# TapTempo.net
KiCad netlist of a schematic drawn in EAGLE
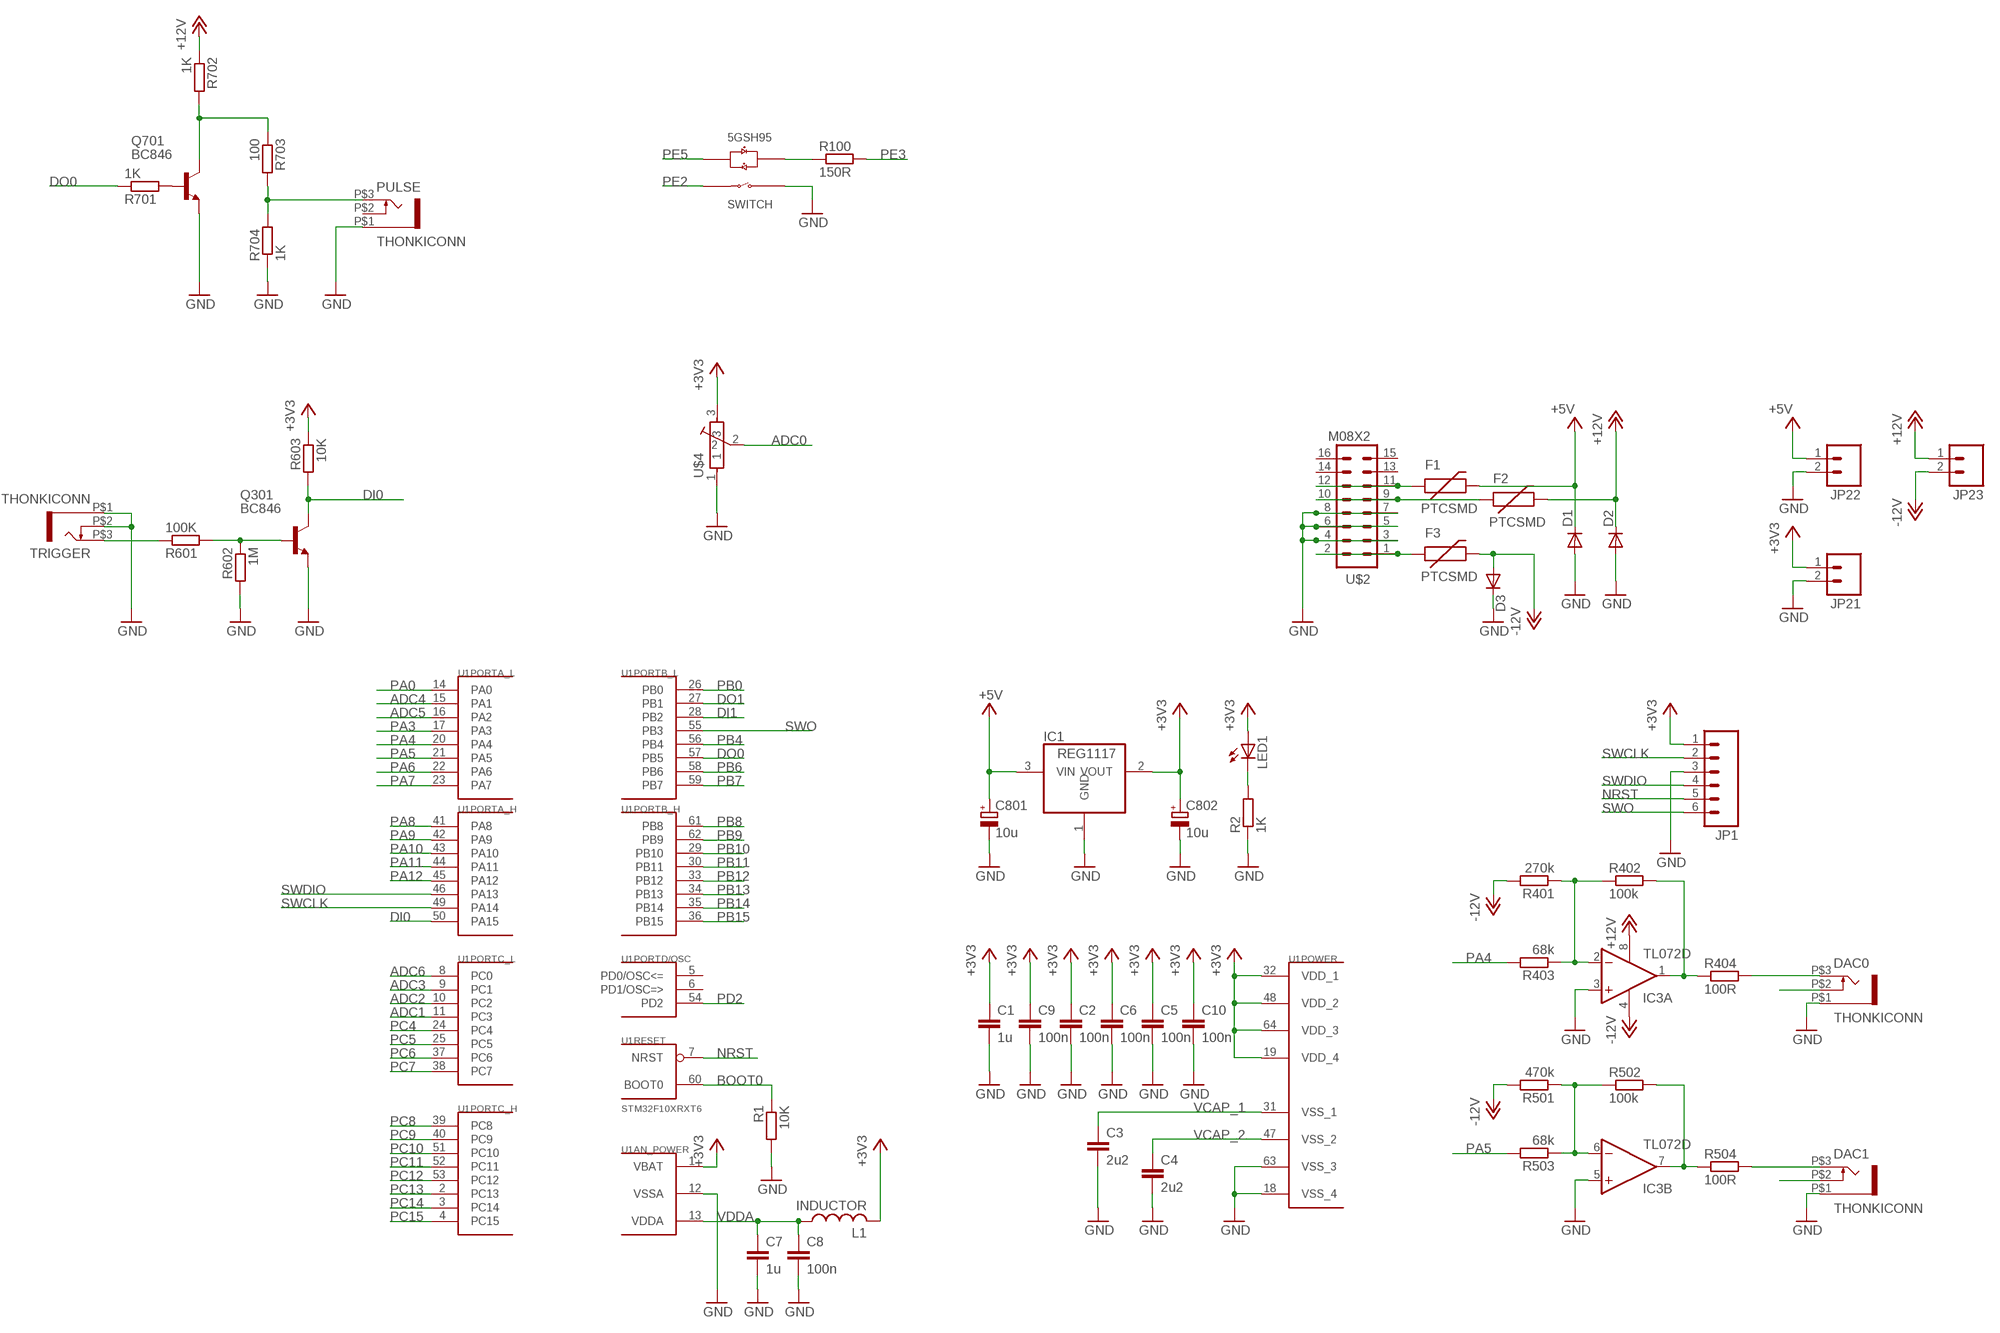
[diagram p0: schematic, sheet 1]

(export (version "E")
  (design (tool "Eeschema 10.0.6"))
  (components
    (comp (ref "C1")
      (value "1u")
      (footprint "eagle-import:C0603")
      (libsource (lib "eagle-import") (part "C-EUC0603"))
    )
    (comp (ref "C2")
      (value "100n")
      (footprint "eagle-import:C0603")
      (libsource (lib "eagle-import") (part "C-EUC0603"))
    )
    (comp (ref "C3")
      (value "2u2")
      (footprint "eagle-import:C0603")
      (libsource (lib "eagle-import") (part "C-EUC0603"))
    )
    (comp (ref "C4")
      (value "2u2")
      (footprint "eagle-import:C0603")
      (libsource (lib "eagle-import") (part "C-EUC0603"))
    )
    (comp (ref "C5")
      (value "100n")
      (footprint "eagle-import:C0603")
      (libsource (lib "eagle-import") (part "C-EUC0603"))
    )
    (comp (ref "C6")
      (value "100n")
      (footprint "eagle-import:C0603")
      (libsource (lib "eagle-import") (part "C-EUC0603"))
    )
    (comp (ref "C7")
      (value "1u")
      (footprint "eagle-import:C0603")
      (libsource (lib "eagle-import") (part "C-EUC0603"))
    )
    (comp (ref "C8")
      (value "100n")
      (footprint "eagle-import:C0603")
      (libsource (lib "eagle-import") (part "C-EUC0603"))
    )
    (comp (ref "C9")
      (value "100n")
      (footprint "eagle-import:C0603")
      (libsource (lib "eagle-import") (part "C-EUC0603"))
    )
    (comp (ref "C10")
      (value "100n")
      (footprint "eagle-import:C0603")
      (libsource (lib "eagle-import") (part "C-EUC0603"))
    )
    (comp (ref "C801")
      (value "10u")
      (footprint "eagle-import:PANASONIC_A")
      (libsource (lib "eagle-import") (part "CPOL-EUA"))
    )
    (comp (ref "C802")
      (value "10u")
      (footprint "eagle-import:PANASONIC_A")
      (libsource (lib "eagle-import") (part "CPOL-EUA"))
    )
    (comp (ref "D1")
      (value "DIODESMA")
      (footprint "eagle-import:SMA-DIODE")
      (libsource (lib "eagle-import") (part "DIODESMA"))
    )
    (comp (ref "D2")
      (value "DIODESMA")
      (footprint "eagle-import:SMA-DIODE")
      (libsource (lib "eagle-import") (part "DIODESMA"))
    )
    (comp (ref "D3")
      (value "DIODESMA")
      (footprint "eagle-import:SMA-DIODE")
      (libsource (lib "eagle-import") (part "DIODESMA"))
    )
    (comp (ref "DAC0")
      (value "THONKICONN")
      (footprint "eagle-import:THONKICONN")
      (libsource (lib "eagle-import") (part "THONKICONN"))
    )
    (comp (ref "DAC1")
      (value "THONKICONN")
      (footprint "eagle-import:THONKICONN")
      (libsource (lib "eagle-import") (part "THONKICONN"))
    )
    (comp (ref "F1")
      (value "PTCSMD")
      (footprint "eagle-import:PTC-1206")
      (libsource (lib "eagle-import") (part "PTCSMD"))
    )
    (comp (ref "F2")
      (value "PTCSMD")
      (footprint "eagle-import:PTC-1206")
      (libsource (lib "eagle-import") (part "PTCSMD"))
    )
    (comp (ref "F3")
      (value "PTCSMD")
      (footprint "eagle-import:PTC-1206")
      (libsource (lib "eagle-import") (part "PTCSMD"))
    )
    (comp (ref "IC1")
      (value "REG1117")
      (footprint "eagle-import:SOT223")
      (libsource (lib "eagle-import") (part "REG1117"))
    )
    (comp (ref "IC3")
      (value "TL072D")
      (footprint "eagle-import:SO08")
      (libsource (lib "eagle-import") (part "TL072D"))
    )
    (comp (ref "JP1")
      (value "M06SIP")
      (footprint "eagle-import:1X06")
      (libsource (lib "eagle-import") (part "M06SIP"))
    )
    (comp (ref "JP21")
      (value "M02PTH")
      (footprint "eagle-import:1X02")
      (libsource (lib "eagle-import") (part "M02PTH"))
    )
    (comp (ref "JP22")
      (value "M02PTH")
      (footprint "eagle-import:1X02")
      (libsource (lib "eagle-import") (part "M02PTH"))
    )
    (comp (ref "JP23")
      (value "M02PTH")
      (footprint "eagle-import:1X02")
      (libsource (lib "eagle-import") (part "M02PTH"))
    )
    (comp (ref "L1")
      (value "INDUCTOR")
      (footprint "eagle-import:0603@1")
      (libsource (lib "eagle-import") (part "INDUCTOR"))
    )
    (comp (ref "LED1")
      (value "LEDCHIPLED_0603")
      (footprint "eagle-import:CHIPLED_0603")
      (libsource (lib "eagle-import") (part "LEDCHIPLED_0603"))
    )
    (comp (ref "PULSE")
      (value "THONKICONN")
      (footprint "eagle-import:THONKICONN")
      (libsource (lib "eagle-import") (part "THONKICONN"))
    )
    (comp (ref "Q301")
      (value "BC846")
      (footprint "eagle-import:SOT23")
      (libsource (lib "eagle-import") (part "BC846"))
    )
    (comp (ref "Q701")
      (value "BC846")
      (footprint "eagle-import:SOT23")
      (libsource (lib "eagle-import") (part "BC846"))
    )
    (comp (ref "R1")
      (value "10K")
      (footprint "eagle-import:R0603")
      (libsource (lib "eagle-import") (part "R-EU_R0603"))
    )
    (comp (ref "R2")
      (value "1K")
      (footprint "eagle-import:R0603")
      (libsource (lib "eagle-import") (part "R-EU_R0603"))
    )
    (comp (ref "R100")
      (value "150R")
      (footprint "eagle-import:0603")
      (libsource (lib "eagle-import") (part "R-EU_0603"))
    )
    (comp (ref "R401")
      (value "270k")
      (footprint "eagle-import:R0603")
      (libsource (lib "eagle-import") (part "R-EU_R0603"))
    )
    (comp (ref "R402")
      (value "100k")
      (footprint "eagle-import:R0603")
      (libsource (lib "eagle-import") (part "R-EU_R0603"))
    )
    (comp (ref "R403")
      (value "68k")
      (footprint "eagle-import:R0603")
      (libsource (lib "eagle-import") (part "R-EU_R0603"))
    )
    (comp (ref "R404")
      (value "100R")
      (footprint "eagle-import:R0603")
      (libsource (lib "eagle-import") (part "R-EU_R0603"))
    )
    (comp (ref "R501")
      (value "470k")
      (footprint "eagle-import:R0603")
      (libsource (lib "eagle-import") (part "R-EU_R0603"))
    )
    (comp (ref "R502")
      (value "100k")
      (footprint "eagle-import:R0603")
      (libsource (lib "eagle-import") (part "R-EU_R0603"))
    )
    (comp (ref "R503")
      (value "68k")
      (footprint "eagle-import:R0603")
      (libsource (lib "eagle-import") (part "R-EU_R0603"))
    )
    (comp (ref "R504")
      (value "100R")
      (footprint "eagle-import:R0603")
      (libsource (lib "eagle-import") (part "R-EU_R0603"))
    )
    (comp (ref "R601")
      (value "100K")
      (footprint "eagle-import:R0603")
      (libsource (lib "eagle-import") (part "R-EU_R0603"))
    )
    (comp (ref "R602")
      (value "1M")
      (footprint "eagle-import:R0603")
      (libsource (lib "eagle-import") (part "R-EU_R0603"))
    )
    (comp (ref "R603")
      (value "10K")
      (footprint "eagle-import:R0603")
      (libsource (lib "eagle-import") (part "R-EU_R0603"))
    )
    (comp (ref "R701")
      (value "1K")
      (footprint "eagle-import:R0603")
      (libsource (lib "eagle-import") (part "R-EU_R0603"))
    )
    (comp (ref "R702")
      (value "1K")
      (footprint "eagle-import:R0603")
      (libsource (lib "eagle-import") (part "R-EU_R0603"))
    )
    (comp (ref "R703")
      (value "100")
      (footprint "eagle-import:R0603")
      (libsource (lib "eagle-import") (part "R-EU_R0603"))
    )
    (comp (ref "R704")
      (value "1K")
      (footprint "eagle-import:R0603")
      (libsource (lib "eagle-import") (part "R-EU_R0603"))
    )
    (comp (ref "TRIGGER")
      (value "THONKICONN")
      (footprint "eagle-import:THONKICONN")
      (libsource (lib "eagle-import") (part "THONKICONN"))
    )
    (comp (ref "U$1")
      (value "5GTH9")
      (footprint "eagle-import:5GTH9")
      (libsource (lib "eagle-import") (part "5GTH9"))
    )
    (comp (ref "U$2")
      (value "M08X2")
      (footprint "eagle-import:2X8")
      (libsource (lib "eagle-import") (part "M08X2"))
    )
    (comp (ref "U$4")
      (value "POT-ALPS-RK09L1140")
      (footprint "eagle-import:POT-ALPS-RK09L1140")
      (libsource (lib "eagle-import") (part "POT-ALPS-RK09L1140"))
    )
    (comp (ref "U1")
      (value "STM32F10XRXT6")
      (footprint "eagle-import:TQFP64")
      (libsource (lib "eagle-import") (part "STM32F10XRXT6"))
    )
  )
  (nets
    (net (code "1") (name "+3V3") (class "Default")
      (node (ref "C1") (pin "1") (pinfunction "1_1") (pintype "passive"))
      (node (ref "C10") (pin "1") (pinfunction "1_1") (pintype "passive"))
      (node (ref "C2") (pin "1") (pinfunction "1_1") (pintype "passive"))
      (node (ref "C5") (pin "1") (pinfunction "1_1") (pintype "passive"))
      (node (ref "C6") (pin "1") (pinfunction "1_1") (pintype "passive"))
      (node (ref "C802") (pin "+") (pinfunction "+_+") (pintype "passive"))
      (node (ref "C9") (pin "1") (pinfunction "1_1") (pintype "passive"))
      (node (ref "IC1") (pin "2") (pinfunction "VOUT_2") (pintype "output"))
      (node (ref "JP1") (pin "1") (pinfunction "1_1") (pintype "passive"))
      (node (ref "JP21") (pin "1") (pinfunction "1_1") (pintype "passive"))
      (node (ref "L1") (pin "2") (pinfunction "2_2") (pintype "passive"))
      (node (ref "LED1") (pin "A") (pinfunction "A_A") (pintype "passive"))
      (node (ref "R603") (pin "1") (pinfunction "1_1") (pintype "passive"))
      (node (ref "U$4") (pin "3") (pinfunction "3_3") (pintype "bidirectional"))
      (node (ref "U1") (pin "1") (pinfunction "VBAT_1") (pintype "power_in"))
      (node (ref "U1") (pin "19") (pinfunction "VDD_4_19") (pintype "power_in"))
      (node (ref "U1") (pin "32") (pinfunction "VDD_1_32") (pintype "power_in"))
      (node (ref "U1") (pin "48") (pinfunction "VDD_2_48") (pintype "power_in"))
      (node (ref "U1") (pin "64") (pinfunction "VDD_3_64") (pintype "power_in"))
    )
    (net (code "2") (name "+5V") (class "Default")
      (node (ref "C801") (pin "+") (pinfunction "+_+") (pintype "passive"))
      (node (ref "D1") (pin "C") (pinfunction "C_C") (pintype "passive"))
      (node (ref "F1") (pin "2") (pinfunction "2_2") (pintype "bidirectional"))
      (node (ref "IC1") (pin "3") (pinfunction "VIN_3") (pintype "input"))
      (node (ref "JP22") (pin "1") (pinfunction "1_1") (pintype "passive"))
    )
    (net (code "3") (name "+12V") (class "Default")
      (node (ref "D2") (pin "C") (pinfunction "C_C") (pintype "passive"))
      (node (ref "F2") (pin "2") (pinfunction "2_2") (pintype "bidirectional"))
      (node (ref "IC3") (pin "8") (pinfunction "V+_8") (pintype "power_in"))
      (node (ref "JP23") (pin "1") (pinfunction "1_1") (pintype "passive"))
      (node (ref "R702") (pin "1") (pinfunction "1_1") (pintype "passive"))
    )
    (net (code "4") (name "-12V") (class "Default")
      (node (ref "D3") (pin "A") (pinfunction "A_A") (pintype "passive"))
      (node (ref "F3") (pin "2") (pinfunction "2_2") (pintype "bidirectional"))
      (node (ref "IC3") (pin "4") (pinfunction "V-_4") (pintype "power_in"))
      (node (ref "JP23") (pin "2") (pinfunction "2_2") (pintype "passive"))
      (node (ref "R401") (pin "2") (pinfunction "2_2") (pintype "passive"))
      (node (ref "R501") (pin "2") (pinfunction "2_2") (pintype "passive"))
    )
    (net (code "5") (name "/ADC0") (class "Default")
      (node (ref "U$4") (pin "2") (pinfunction "2_2") (pintype "bidirectional"))
    )
    (net (code "6") (name "/ADC1") (class "Default")
      (node (ref "U1") (pin "11") (pinfunction "PC3_11") (pintype "bidirectional"))
    )
    (net (code "7") (name "/ADC2") (class "Default")
      (node (ref "U1") (pin "10") (pinfunction "PC2_10") (pintype "bidirectional"))
    )
    (net (code "8") (name "/ADC3") (class "Default")
      (node (ref "U1") (pin "9") (pinfunction "PC1_9") (pintype "bidirectional"))
    )
    (net (code "9") (name "/ADC4") (class "Default")
      (node (ref "U1") (pin "15") (pinfunction "PA1_15") (pintype "bidirectional"))
    )
    (net (code "10") (name "/ADC5") (class "Default")
      (node (ref "U1") (pin "16") (pinfunction "PA2_16") (pintype "bidirectional"))
    )
    (net (code "11") (name "/ADC6") (class "Default")
      (node (ref "U1") (pin "8") (pinfunction "PC0_8") (pintype "bidirectional"))
    )
    (net (code "12") (name "/BOOT0") (class "Default")
      (node (ref "R1") (pin "1") (pinfunction "1_1") (pintype "passive"))
      (node (ref "U1") (pin "60") (pinfunction "BOOT0_60") (pintype "input"))
    )
    (net (code "13") (name "/DI0") (class "Default")
      (node (ref "Q301") (pin "3") (pinfunction "C_3") (pintype "passive"))
      (node (ref "R603") (pin "2") (pinfunction "2_2") (pintype "passive"))
      (node (ref "U1") (pin "50") (pinfunction "PA15_50") (pintype "bidirectional"))
    )
    (net (code "14") (name "/DI1") (class "Default")
      (node (ref "U1") (pin "28") (pinfunction "PB2_28") (pintype "bidirectional"))
    )
    (net (code "15") (name "/DO0") (class "Default")
      (node (ref "R701") (pin "1") (pinfunction "1_1") (pintype "passive"))
      (node (ref "U1") (pin "57") (pinfunction "PB5_57") (pintype "bidirectional"))
    )
    (net (code "16") (name "/DO1") (class "Default")
      (node (ref "U1") (pin "27") (pinfunction "PB1_27") (pintype "bidirectional"))
    )
    (net (code "17") (name "/NRST") (class "Default")
      (node (ref "JP1") (pin "5") (pinfunction "5_5") (pintype "passive"))
      (node (ref "U1") (pin "7") (pinfunction "NRST_7") (pintype "input"))
    )
    (net (code "18") (name "/PA0") (class "Default")
      (node (ref "U1") (pin "14") (pinfunction "PA0_14") (pintype "bidirectional"))
    )
    (net (code "19") (name "/PA3") (class "Default")
      (node (ref "U1") (pin "17") (pinfunction "PA3_17") (pintype "bidirectional"))
    )
    (net (code "20") (name "/PA4") (class "Default")
      (node (ref "R403") (pin "2") (pinfunction "2_2") (pintype "passive"))
      (node (ref "U1") (pin "20") (pinfunction "PA4_20") (pintype "bidirectional"))
    )
    (net (code "21") (name "/PA5") (class "Default")
      (node (ref "R503") (pin "2") (pinfunction "2_2") (pintype "passive"))
      (node (ref "U1") (pin "21") (pinfunction "PA5_21") (pintype "bidirectional"))
    )
    (net (code "22") (name "/PA6") (class "Default")
      (node (ref "U1") (pin "22") (pinfunction "PA6_22") (pintype "bidirectional"))
    )
    (net (code "23") (name "/PA7") (class "Default")
      (node (ref "U1") (pin "23") (pinfunction "PA7_23") (pintype "bidirectional"))
    )
    (net (code "24") (name "/PA8") (class "Default")
      (node (ref "U1") (pin "41") (pinfunction "PA8_41") (pintype "bidirectional"))
    )
    (net (code "25") (name "/PA9") (class "Default")
      (node (ref "U1") (pin "42") (pinfunction "PA9_42") (pintype "bidirectional"))
    )
    (net (code "26") (name "/PA10") (class "Default")
      (node (ref "U1") (pin "43") (pinfunction "PA10_43") (pintype "bidirectional"))
    )
    (net (code "27") (name "/PA11") (class "Default")
      (node (ref "U1") (pin "44") (pinfunction "PA11_44") (pintype "bidirectional"))
    )
    (net (code "28") (name "/PA12") (class "Default")
      (node (ref "U1") (pin "45") (pinfunction "PA12_45") (pintype "bidirectional"))
    )
    (net (code "29") (name "/PB0") (class "Default")
      (node (ref "U1") (pin "26") (pinfunction "PB0_26") (pintype "bidirectional"))
    )
    (net (code "30") (name "/PB4") (class "Default")
      (node (ref "U1") (pin "56") (pinfunction "PB4_56") (pintype "bidirectional"))
    )
    (net (code "31") (name "/PB6") (class "Default")
      (node (ref "U1") (pin "58") (pinfunction "PB6_58") (pintype "bidirectional"))
    )
    (net (code "32") (name "/PB7") (class "Default")
      (node (ref "U1") (pin "59") (pinfunction "PB7_59") (pintype "bidirectional"))
    )
    (net (code "33") (name "/PB8") (class "Default")
      (node (ref "U1") (pin "61") (pinfunction "PB8_61") (pintype "bidirectional"))
    )
    (net (code "34") (name "/PB9") (class "Default")
      (node (ref "U1") (pin "62") (pinfunction "PB9_62") (pintype "bidirectional"))
    )
    (net (code "35") (name "/PB10") (class "Default")
      (node (ref "U1") (pin "29") (pinfunction "PB10_29") (pintype "bidirectional"))
    )
    (net (code "36") (name "/PB11") (class "Default")
      (node (ref "U1") (pin "30") (pinfunction "PB11_30") (pintype "bidirectional"))
    )
    (net (code "37") (name "/PB12") (class "Default")
      (node (ref "U1") (pin "33") (pinfunction "PB12_33") (pintype "bidirectional"))
    )
    (net (code "38") (name "/PB13") (class "Default")
      (node (ref "U1") (pin "34") (pinfunction "PB13_34") (pintype "bidirectional"))
    )
    (net (code "39") (name "/PB14") (class "Default")
      (node (ref "U1") (pin "35") (pinfunction "PB14_35") (pintype "bidirectional"))
    )
    (net (code "40") (name "/PB15") (class "Default")
      (node (ref "U1") (pin "36") (pinfunction "PB15_36") (pintype "bidirectional"))
    )
    (net (code "41") (name "/PC4") (class "Default")
      (node (ref "U1") (pin "24") (pinfunction "PC4_24") (pintype "bidirectional"))
    )
    (net (code "42") (name "/PC5") (class "Default")
      (node (ref "U1") (pin "25") (pinfunction "PC5_25") (pintype "bidirectional"))
    )
    (net (code "43") (name "/PC6") (class "Default")
      (node (ref "U1") (pin "37") (pinfunction "PC6_37") (pintype "bidirectional"))
    )
    (net (code "44") (name "/PC7") (class "Default")
      (node (ref "U1") (pin "38") (pinfunction "PC7_38") (pintype "bidirectional"))
    )
    (net (code "45") (name "/PC8") (class "Default")
      (node (ref "U1") (pin "39") (pinfunction "PC8_39") (pintype "bidirectional"))
    )
    (net (code "46") (name "/PC9") (class "Default")
      (node (ref "U1") (pin "40") (pinfunction "PC9_40") (pintype "bidirectional"))
    )
    (net (code "47") (name "/PC10") (class "Default")
      (node (ref "U1") (pin "51") (pinfunction "PC10_51") (pintype "bidirectional"))
    )
    (net (code "48") (name "/PC11") (class "Default")
      (node (ref "U1") (pin "52") (pinfunction "PC11_52") (pintype "bidirectional"))
    )
    (net (code "49") (name "/PC12") (class "Default")
      (node (ref "U1") (pin "53") (pinfunction "PC12_53") (pintype "bidirectional"))
    )
    (net (code "50") (name "/PC13") (class "Default")
      (node (ref "U1") (pin "2") (pinfunction "PC13_2") (pintype "bidirectional"))
    )
    (net (code "51") (name "/PC14") (class "Default")
      (node (ref "U1") (pin "3") (pinfunction "PC14_3") (pintype "bidirectional"))
    )
    (net (code "52") (name "/PC15") (class "Default")
      (node (ref "U1") (pin "4") (pinfunction "PC15_4") (pintype "bidirectional"))
    )
    (net (code "53") (name "/PD2") (class "Default")
      (node (ref "U1") (pin "54") (pinfunction "PD2_54") (pintype "bidirectional"))
    )
    (net (code "54") (name "/PE2") (class "Default")
      (node (ref "U$1") (pin "4") (pinfunction "SWITCH_A_4") (pintype "power_in"))
    )
    (net (code "55") (name "/PE3") (class "Default")
      (node (ref "R100") (pin "2") (pinfunction "2_2") (pintype "passive"))
    )
    (net (code "56") (name "/PE5") (class "Default")
      (node (ref "U$1") (pin "-2") (pinfunction "LED_G+_-2") (pintype "input"))
    )
    (net (code "57") (name "/SWCLK") (class "Default")
      (node (ref "JP1") (pin "2") (pinfunction "2_2") (pintype "passive"))
      (node (ref "U1") (pin "49") (pinfunction "PA14_49") (pintype "bidirectional"))
    )
    (net (code "58") (name "/SWDIO") (class "Default")
      (node (ref "JP1") (pin "4") (pinfunction "4_4") (pintype "passive"))
      (node (ref "U1") (pin "46") (pinfunction "PA13_46") (pintype "bidirectional"))
    )
    (net (code "59") (name "/SWO") (class "Default")
      (node (ref "JP1") (pin "6") (pinfunction "6_6") (pintype "passive"))
      (node (ref "U1") (pin "55") (pinfunction "PB3_55") (pintype "bidirectional"))
    )
    (net (code "60") (name "/VCAP_1") (class "Default")
      (node (ref "C3") (pin "1") (pinfunction "1_1") (pintype "passive"))
      (node (ref "U1") (pin "31") (pinfunction "VSS_1_31") (pintype "power_in"))
    )
    (net (code "61") (name "/VCAP_2") (class "Default")
      (node (ref "C4") (pin "1") (pinfunction "1_1") (pintype "passive"))
      (node (ref "U1") (pin "47") (pinfunction "VSS_2_47") (pintype "power_in"))
    )
    (net (code "62") (name "/VDDA") (class "Default")
      (node (ref "C7") (pin "1") (pinfunction "1_1") (pintype "passive"))
      (node (ref "C8") (pin "1") (pinfunction "1_1") (pintype "passive"))
      (node (ref "L1") (pin "1") (pinfunction "1_1") (pintype "passive"))
      (node (ref "U1") (pin "13") (pinfunction "VDDA_13") (pintype "power_in"))
    )
    (net (code "63") (name "GND") (class "Default")
      (node (ref "C1") (pin "2") (pinfunction "2_2") (pintype "passive"))
      (node (ref "C10") (pin "2") (pinfunction "2_2") (pintype "passive"))
      (node (ref "C2") (pin "2") (pinfunction "2_2") (pintype "passive"))
      (node (ref "C3") (pin "2") (pinfunction "2_2") (pintype "passive"))
      (node (ref "C4") (pin "2") (pinfunction "2_2") (pintype "passive"))
      (node (ref "C5") (pin "2") (pinfunction "2_2") (pintype "passive"))
      (node (ref "C6") (pin "2") (pinfunction "2_2") (pintype "passive"))
      (node (ref "C7") (pin "2") (pinfunction "2_2") (pintype "passive"))
      (node (ref "C8") (pin "2") (pinfunction "2_2") (pintype "passive"))
      (node (ref "C801") (pin "-") (pinfunction "-_-") (pintype "passive"))
      (node (ref "C802") (pin "-") (pinfunction "-_-") (pintype "passive"))
      (node (ref "C9") (pin "2") (pinfunction "2_2") (pintype "passive"))
      (node (ref "D1") (pin "A") (pinfunction "A_A") (pintype "passive"))
      (node (ref "D2") (pin "A") (pinfunction "A_A") (pintype "passive"))
      (node (ref "D3") (pin "C") (pinfunction "C_C") (pintype "passive"))
      (node (ref "DAC0") (pin "P$1") (pinfunction "5_P$1") (pintype "passive"))
      (node (ref "DAC1") (pin "P$1") (pinfunction "5_P$1") (pintype "passive"))
      (node (ref "IC1") (pin "1") (pinfunction "GND_1") (pintype "power_in"))
      (node (ref "IC3") (pin "3") (pinfunction "+IN_3") (pintype "input"))
      (node (ref "IC3") (pin "5") (pinfunction "+IN_5") (pintype "input"))
      (node (ref "JP1") (pin "3") (pinfunction "3_3") (pintype "passive"))
      (node (ref "JP21") (pin "2") (pinfunction "2_2") (pintype "passive"))
      (node (ref "JP22") (pin "2") (pinfunction "2_2") (pintype "passive"))
      (node (ref "PULSE") (pin "P$1") (pinfunction "5_P$1") (pintype "passive"))
      (node (ref "Q301") (pin "2") (pinfunction "E_2") (pintype "passive"))
      (node (ref "Q701") (pin "2") (pinfunction "E_2") (pintype "passive"))
      (node (ref "R1") (pin "2") (pinfunction "2_2") (pintype "passive"))
      (node (ref "R2") (pin "1") (pinfunction "1_1") (pintype "passive"))
      (node (ref "R602") (pin "2") (pinfunction "2_2") (pintype "passive"))
      (node (ref "R704") (pin "1") (pinfunction "1_1") (pintype "passive"))
      (node (ref "TRIGGER") (pin "P$1") (pinfunction "5_P$1") (pintype "passive"))
      (node (ref "TRIGGER") (pin "P$2") (pinfunction "4_P$2") (pintype "passive"))
      (node (ref "U$1") (pin "1") (pinfunction "SWITCH_B_1") (pintype "power_in"))
      (node (ref "U$2") (pin "3") (pinfunction "3_3") (pintype "passive"))
      (node (ref "U$2") (pin "4") (pinfunction "4_4") (pintype "passive"))
      (node (ref "U$2") (pin "5") (pinfunction "5_5") (pintype "passive"))
      (node (ref "U$2") (pin "6") (pinfunction "6_6") (pintype "passive"))
      (node (ref "U$2") (pin "7") (pinfunction "7_7") (pintype "passive"))
      (node (ref "U$2") (pin "8") (pinfunction "8_8") (pintype "passive"))
      (node (ref "U$4") (pin "1") (pinfunction "1_1") (pintype "bidirectional"))
      (node (ref "U1") (pin "12") (pinfunction "VSSA_12") (pintype "power_in"))
      (node (ref "U1") (pin "18") (pinfunction "VSS_4_18") (pintype "power_in"))
      (node (ref "U1") (pin "63") (pinfunction "VSS_3_63") (pintype "power_in"))
    )
    (net (code "64") (name "Net-(DAC0-3)") (class "Default")
      (node (ref "DAC0") (pin "P$3") (pinfunction "3_P$3") (pintype "passive"))
      (node (ref "R404") (pin "2") (pinfunction "2_2") (pintype "passive"))
    )
    (net (code "65") (name "Net-(DAC1-3)") (class "Default")
      (node (ref "DAC1") (pin "P$3") (pinfunction "3_P$3") (pintype "passive"))
      (node (ref "R504") (pin "2") (pinfunction "2_2") (pintype "passive"))
    )
    (net (code "66") (name "Net-(F1-Pad1)") (class "Default")
      (node (ref "F1") (pin "1") (pinfunction "1_1") (pintype "bidirectional"))
      (node (ref "U$2") (pin "11") (pinfunction "11_11") (pintype "passive"))
      (node (ref "U$2") (pin "12") (pinfunction "12_12") (pintype "passive"))
    )
    (net (code "67") (name "Net-(F2-Pad1)") (class "Default")
      (node (ref "F2") (pin "1") (pinfunction "1_1") (pintype "bidirectional"))
      (node (ref "U$2") (pin "10") (pinfunction "10_10") (pintype "passive"))
      (node (ref "U$2") (pin "9") (pinfunction "9_9") (pintype "passive"))
    )
    (net (code "68") (name "Net-(F3-Pad1)") (class "Default")
      (node (ref "F3") (pin "1") (pinfunction "1_1") (pintype "bidirectional"))
      (node (ref "U$2") (pin "1") (pinfunction "1_1") (pintype "passive"))
      (node (ref "U$2") (pin "2") (pinfunction "2_2") (pintype "passive"))
    )
    (net (code "69") (name "Net-(IC3A--IN)") (class "Default")
      (node (ref "IC3") (pin "2") (pinfunction "-IN_2") (pintype "input"))
      (node (ref "R401") (pin "1") (pinfunction "1_1") (pintype "passive"))
      (node (ref "R402") (pin "1") (pinfunction "1_1") (pintype "passive"))
      (node (ref "R403") (pin "1") (pinfunction "1_1") (pintype "passive"))
    )
    (net (code "70") (name "Net-(IC3A-OUT)") (class "Default")
      (node (ref "IC3") (pin "1") (pinfunction "OUT_1") (pintype "output"))
      (node (ref "R402") (pin "2") (pinfunction "2_2") (pintype "passive"))
      (node (ref "R404") (pin "1") (pinfunction "1_1") (pintype "passive"))
    )
    (net (code "71") (name "Net-(IC3B--IN)") (class "Default")
      (node (ref "IC3") (pin "6") (pinfunction "-IN_6") (pintype "input"))
      (node (ref "R501") (pin "1") (pinfunction "1_1") (pintype "passive"))
      (node (ref "R502") (pin "1") (pinfunction "1_1") (pintype "passive"))
      (node (ref "R503") (pin "1") (pinfunction "1_1") (pintype "passive"))
    )
    (net (code "72") (name "Net-(IC3B-OUT)") (class "Default")
      (node (ref "IC3") (pin "7") (pinfunction "OUT_7") (pintype "output"))
      (node (ref "R502") (pin "2") (pinfunction "2_2") (pintype "passive"))
      (node (ref "R504") (pin "1") (pinfunction "1_1") (pintype "passive"))
    )
    (net (code "73") (name "Net-(LED1-PadC)") (class "Default")
      (node (ref "LED1") (pin "C") (pinfunction "C_C") (pintype "passive"))
      (node (ref "R2") (pin "2") (pinfunction "2_2") (pintype "passive"))
    )
    (net (code "74") (name "Net-(PULSE-3)") (class "Default")
      (node (ref "PULSE") (pin "P$3") (pinfunction "3_P$3") (pintype "passive"))
      (node (ref "R703") (pin "2") (pinfunction "2_2") (pintype "passive"))
      (node (ref "R704") (pin "2") (pinfunction "2_2") (pintype "passive"))
    )
    (net (code "75") (name "Net-(Q301-B)") (class "Default")
      (node (ref "Q301") (pin "1") (pinfunction "B_1") (pintype "passive"))
      (node (ref "R601") (pin "2") (pinfunction "2_2") (pintype "passive"))
      (node (ref "R602") (pin "1") (pinfunction "1_1") (pintype "passive"))
    )
    (net (code "76") (name "Net-(Q701-B)") (class "Default")
      (node (ref "Q701") (pin "1") (pinfunction "B_1") (pintype "passive"))
      (node (ref "R701") (pin "2") (pinfunction "2_2") (pintype "passive"))
    )
    (net (code "77") (name "Net-(Q701-C)") (class "Default")
      (node (ref "Q701") (pin "3") (pinfunction "C_3") (pintype "passive"))
      (node (ref "R702") (pin "2") (pinfunction "2_2") (pintype "passive"))
      (node (ref "R703") (pin "1") (pinfunction "1_1") (pintype "passive"))
    )
    (net (code "78") (name "Net-(TRIGGER-3)") (class "Default")
      (node (ref "R601") (pin "1") (pinfunction "1_1") (pintype "passive"))
      (node (ref "TRIGGER") (pin "P$3") (pinfunction "3_P$3") (pintype "passive"))
    )
    (net (code "79") (name "Net-(U$1-LED_R+)") (class "Default")
      (node (ref "R100") (pin "1") (pinfunction "1_1") (pintype "passive"))
      (node (ref "U$1") (pin "+3") (pinfunction "LED_R+_+3") (pintype "input"))
    )
    (net (code "80") (name "unconnected-(DAC0-4-PadP$2)") (class "Default")
      (node (ref "DAC0") (pin "P$2") (pinfunction "4_P$2") (pintype "passive"))
    )
    (net (code "81") (name "unconnected-(DAC1-4-PadP$2)") (class "Default")
      (node (ref "DAC1") (pin "P$2") (pinfunction "4_P$2") (pintype "passive"))
    )
    (net (code "82") (name "unconnected-(PULSE-4-PadP$2)") (class "Default")
      (node (ref "PULSE") (pin "P$2") (pinfunction "4_P$2") (pintype "passive"))
    )
    (net (code "83") (name "unconnected-(U$2-Pad13)") (class "Default")
      (node (ref "U$2") (pin "13") (pinfunction "13_13") (pintype "passive"))
    )
    (net (code "84") (name "unconnected-(U$2-Pad14)") (class "Default")
      (node (ref "U$2") (pin "14") (pinfunction "14_14") (pintype "passive"))
    )
    (net (code "85") (name "unconnected-(U$2-Pad15)") (class "Default")
      (node (ref "U$2") (pin "15") (pinfunction "15_15") (pintype "passive"))
    )
    (net (code "86") (name "unconnected-(U$2-Pad16)") (class "Default")
      (node (ref "U$2") (pin "16") (pinfunction "16_16") (pintype "passive"))
    )
    (net (code "87") (name "unconnected-(U1H-PD0{slash}OSC<=-Pad5)") (class "Default")
      (node (ref "U1") (pin "5") (pinfunction "PD0/OSC<=_5") (pintype "bidirectional"))
    )
    (net (code "88") (name "unconnected-(U1H-PD1{slash}OSC=>-Pad6)") (class "Default")
      (node (ref "U1") (pin "6") (pinfunction "PD1/OSC=>_6") (pintype "bidirectional"))
    )
  )
)
